# KissCart64-8K-MCU.net
KiCad netlist of a schematic drawn in EAGLE
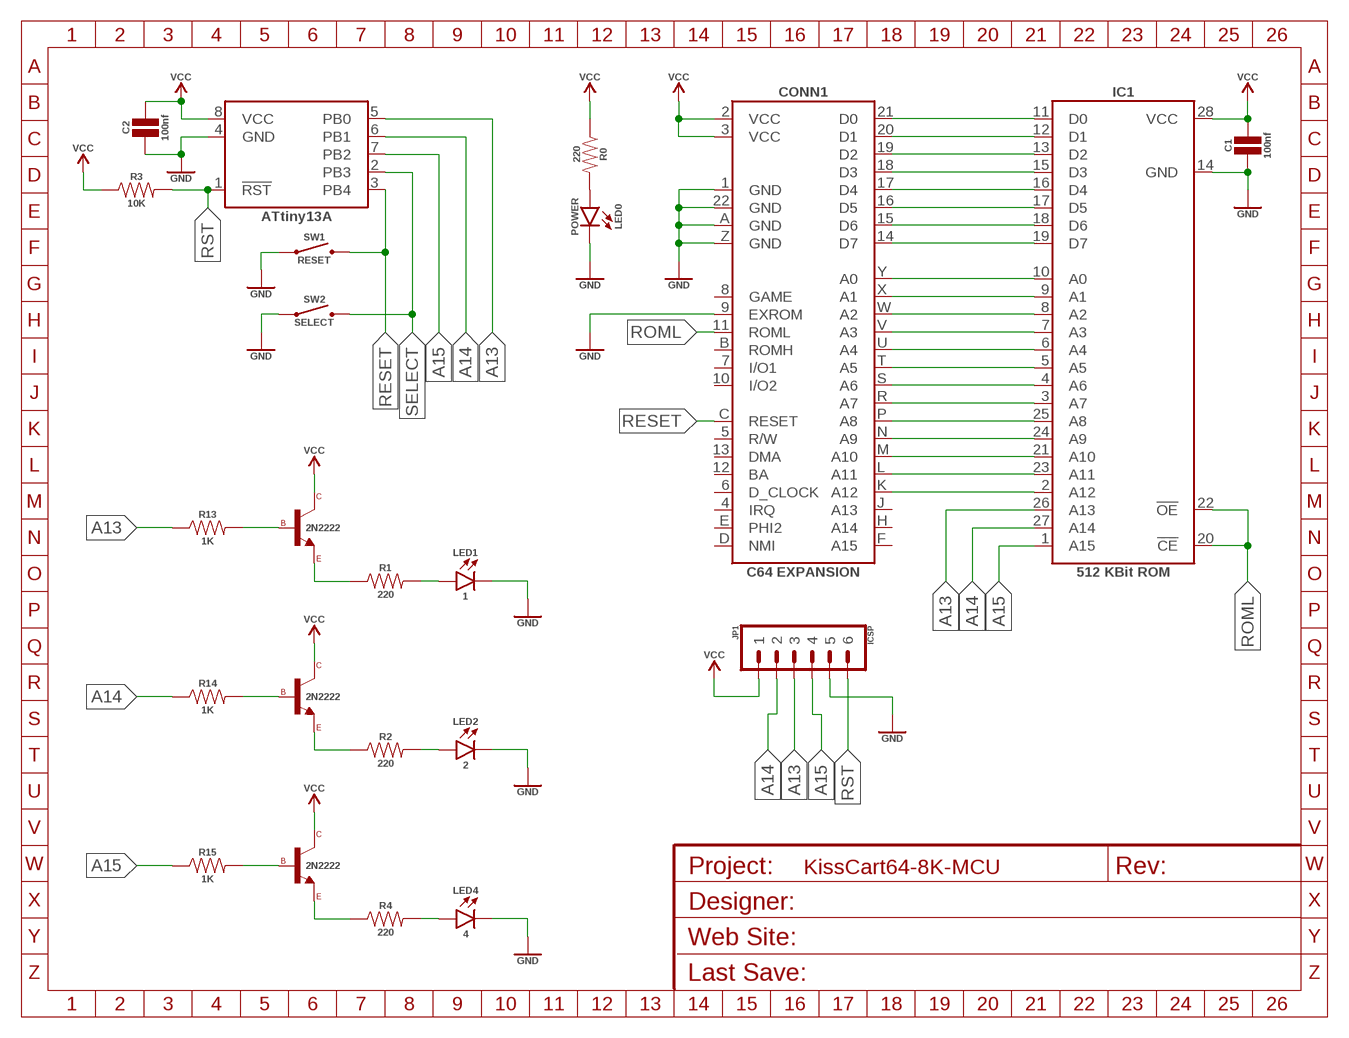
[diagram p0: schematic, sheet 1]

(export (version "E")
  (design (tool "Eeschema 10.0.6"))
  (components
    (comp (ref "C1")
      (value "100nf")
      (footprint "eagle-import:CAPACITOR_CERAMIC_0.2")
      (libsource (lib "eagle-import") (part "CAPACITOR_CERAMIC_0.2"))
    )
    (comp (ref "C2")
      (value "100nf")
      (footprint "eagle-import:CAPACITOR_CERAMIC_1206")
      (libsource (lib "eagle-import") (part "CAPACITOR_CERAMIC_1206"))
    )
    (comp (ref "CONN1")
      (value "C64 EXPANSION")
      (footprint "eagle-import:C64_CARTRIDGE")
      (libsource (lib "eagle-import") (part "C64_CARTDRIGE"))
    )
    (comp (ref "IC1")
      (value "512 KBit ROM")
      (footprint "eagle-import:DIP28W")
      (libsource (lib "eagle-import") (part "27C512_DIP"))
    )
    (comp (ref "IC2")
      (value "ATtiny13A")
      (footprint "eagle-import:SOP08")
      (libsource (lib "eagle-import") (part "ATTINY13A-SU"))
    )
    (comp (ref "JP1")
      (value "ICSP")
      (footprint "eagle-import:HDR_2X03")
      (libsource (lib "eagle-import") (part "HDR_2X03"))
    )
    (comp (ref "LED0")
      (value "POWER")
      (footprint "eagle-import:LED_1206")
      (libsource (lib "eagle-import") (part "LED_NORMAL_1206"))
    )
    (comp (ref "LED1")
      (value "1")
      (footprint "eagle-import:LED_1206")
      (libsource (lib "eagle-import") (part "LED_NORMAL_1206"))
    )
    (comp (ref "LED2")
      (value "2")
      (footprint "eagle-import:LED_1206")
      (libsource (lib "eagle-import") (part "LED_NORMAL_1206"))
    )
    (comp (ref "LED4")
      (value "4")
      (footprint "eagle-import:LED_1206")
      (libsource (lib "eagle-import") (part "LED_NORMAL_1206"))
    )
    (comp (ref "Q1")
      (value "2N2222")
      (footprint "eagle-import:SOT-23")
      (libsource (lib "eagle-import") (part "TRANSISTOR_NPN_MMBT2222A"))
    )
    (comp (ref "Q2")
      (value "2N2222")
      (footprint "eagle-import:SOT-23")
      (libsource (lib "eagle-import") (part "TRANSISTOR_NPN_MMBT2222A"))
    )
    (comp (ref "Q3")
      (value "2N2222")
      (footprint "eagle-import:SOT-23")
      (libsource (lib "eagle-import") (part "TRANSISTOR_NPN_MMBT2222A"))
    )
    (comp (ref "R0")
      (value "220")
      (footprint "eagle-import:RESISTOR_SMT_1206")
      (libsource (lib "eagle-import") (part "RESISTOR_SMT_1206"))
    )
    (comp (ref "R1")
      (value "220")
      (footprint "eagle-import:RESISTOR_SMT_1206")
      (libsource (lib "eagle-import") (part "RESISTOR_SMT_1206"))
    )
    (comp (ref "R2")
      (value "220")
      (footprint "eagle-import:RESISTOR_SMT_1206")
      (libsource (lib "eagle-import") (part "RESISTOR_SMT_1206"))
    )
    (comp (ref "R3")
      (value "10K")
      (footprint "eagle-import:RESISTOR_SMT_1206")
      (libsource (lib "eagle-import") (part "RESISTOR_SMT_1206"))
    )
    (comp (ref "R4")
      (value "220")
      (footprint "eagle-import:RESISTOR_SMT_1206")
      (libsource (lib "eagle-import") (part "RESISTOR_SMT_1206"))
    )
    (comp (ref "R13")
      (value "1K")
      (footprint "eagle-import:RESISTOR_SMT_1206")
      (libsource (lib "eagle-import") (part "RESISTOR_SMT_1206"))
    )
    (comp (ref "R14")
      (value "1K")
      (footprint "eagle-import:RESISTOR_SMT_1206")
      (libsource (lib "eagle-import") (part "RESISTOR_SMT_1206"))
    )
    (comp (ref "R15")
      (value "1K")
      (footprint "eagle-import:RESISTOR_SMT_1206")
      (libsource (lib "eagle-import") (part "RESISTOR_SMT_1206"))
    )
    (comp (ref "SW1")
      (value "RESET")
      (footprint "eagle-import:SWITCH_THT_SIDE")
      (libsource (lib "eagle-import") (part "SWITCH_THT_SIDE"))
    )
    (comp (ref "SW2")
      (value "SELECT")
      (footprint "eagle-import:SWITCH_THT_SIDE")
      (libsource (lib "eagle-import") (part "SWITCH_THT_SIDE"))
    )
  )
  (nets
    (net (code "1") (name "A13") (class "Default")
      (node (ref "IC1") (pin "26") (pinfunction "A13_26") (pintype "input"))
      (node (ref "IC2") (pin "5") (pinfunction "PB0_5") (pintype "bidirectional"))
      (node (ref "JP1") (pin "3") (pinfunction "3_3") (pintype "passive"))
      (node (ref "R13") (pin "1") (pinfunction "1_1") (pintype "passive"))
    )
    (net (code "2") (name "A14") (class "Default")
      (node (ref "IC1") (pin "27") (pinfunction "A14_27") (pintype "input"))
      (node (ref "IC2") (pin "6") (pinfunction "PB1_6") (pintype "bidirectional"))
      (node (ref "JP1") (pin "2") (pinfunction "2_2") (pintype "passive"))
      (node (ref "R14") (pin "1") (pinfunction "1_1") (pintype "passive"))
    )
    (net (code "3") (name "A15") (class "Default")
      (node (ref "IC1") (pin "1") (pinfunction "A15_1") (pintype "input"))
      (node (ref "IC2") (pin "7") (pinfunction "PB2_7") (pintype "bidirectional"))
      (node (ref "JP1") (pin "4") (pinfunction "4_4") (pintype "passive"))
      (node (ref "R15") (pin "1") (pinfunction "1_1") (pintype "passive"))
    )
    (net (code "4") (name "GND") (class "Default")
      (node (ref "C1") (pin "1") (pinfunction "1_1") (pintype "passive"))
      (node (ref "C2") (pin "1") (pinfunction "1_1") (pintype "passive"))
      (node (ref "CONN1") (pin "1") (pinfunction "GND_1") (pintype "bidirectional"))
      (node (ref "CONN1") (pin "22") (pinfunction "GND_22") (pintype "bidirectional"))
      (node (ref "CONN1") (pin "9") (pinfunction "EXROM_9") (pintype "bidirectional"))
      (node (ref "CONN1") (pin "A") (pinfunction "GND_A") (pintype "bidirectional"))
      (node (ref "CONN1") (pin "Z") (pinfunction "GND_Z") (pintype "bidirectional"))
      (node (ref "IC1") (pin "14") (pinfunction "GND_14") (pintype "power_in"))
      (node (ref "IC2") (pin "4") (pinfunction "GND_4") (pintype "power_in"))
      (node (ref "JP1") (pin "5") (pinfunction "5_5") (pintype "passive"))
      (node (ref "LED0") (pin "C") (pinfunction "C_C") (pintype "passive"))
      (node (ref "LED1") (pin "C") (pinfunction "C_C") (pintype "passive"))
      (node (ref "LED2") (pin "C") (pinfunction "C_C") (pintype "passive"))
      (node (ref "LED4") (pin "C") (pinfunction "C_C") (pintype "passive"))
      (node (ref "SW1") (pin "1") (pinfunction "1_1") (pintype "passive"))
      (node (ref "SW2") (pin "1") (pinfunction "1_1") (pintype "passive"))
    )
    (net (code "5") (name "Net-(CONN1-A0)") (class "Default")
      (node (ref "CONN1") (pin "Y") (pinfunction "A0_Y") (pintype "bidirectional"))
      (node (ref "IC1") (pin "10") (pinfunction "A0_10") (pintype "input"))
    )
    (net (code "6") (name "Net-(CONN1-A1)") (class "Default")
      (node (ref "CONN1") (pin "X") (pinfunction "A1_X") (pintype "bidirectional"))
      (node (ref "IC1") (pin "9") (pinfunction "A1_9") (pintype "input"))
    )
    (net (code "7") (name "Net-(CONN1-A2)") (class "Default")
      (node (ref "CONN1") (pin "W") (pinfunction "A2_W") (pintype "bidirectional"))
      (node (ref "IC1") (pin "8") (pinfunction "A2_8") (pintype "input"))
    )
    (net (code "8") (name "Net-(CONN1-A3)") (class "Default")
      (node (ref "CONN1") (pin "V") (pinfunction "A3_V") (pintype "bidirectional"))
      (node (ref "IC1") (pin "7") (pinfunction "A3_7") (pintype "input"))
    )
    (net (code "9") (name "Net-(CONN1-A4)") (class "Default")
      (node (ref "CONN1") (pin "U") (pinfunction "A4_U") (pintype "bidirectional"))
      (node (ref "IC1") (pin "6") (pinfunction "A4_6") (pintype "input"))
    )
    (net (code "10") (name "Net-(CONN1-A5)") (class "Default")
      (node (ref "CONN1") (pin "T") (pinfunction "A5_T") (pintype "bidirectional"))
      (node (ref "IC1") (pin "5") (pinfunction "A5_5") (pintype "input"))
    )
    (net (code "11") (name "Net-(CONN1-A6)") (class "Default")
      (node (ref "CONN1") (pin "S") (pinfunction "A6_S") (pintype "bidirectional"))
      (node (ref "IC1") (pin "4") (pinfunction "A6_4") (pintype "input"))
    )
    (net (code "12") (name "Net-(CONN1-A7)") (class "Default")
      (node (ref "CONN1") (pin "R") (pinfunction "A7_R") (pintype "bidirectional"))
      (node (ref "IC1") (pin "3") (pinfunction "A7_3") (pintype "input"))
    )
    (net (code "13") (name "Net-(CONN1-A8)") (class "Default")
      (node (ref "CONN1") (pin "P") (pinfunction "A8_P") (pintype "bidirectional"))
      (node (ref "IC1") (pin "25") (pinfunction "A8_25") (pintype "input"))
    )
    (net (code "14") (name "Net-(CONN1-A9)") (class "Default")
      (node (ref "CONN1") (pin "N") (pinfunction "A9_N") (pintype "bidirectional"))
      (node (ref "IC1") (pin "24") (pinfunction "A9_24") (pintype "input"))
    )
    (net (code "15") (name "Net-(CONN1-A10)") (class "Default")
      (node (ref "CONN1") (pin "M") (pinfunction "A10_M") (pintype "bidirectional"))
      (node (ref "IC1") (pin "21") (pinfunction "A10_21") (pintype "input"))
    )
    (net (code "16") (name "Net-(CONN1-A11)") (class "Default")
      (node (ref "CONN1") (pin "L") (pinfunction "A11_L") (pintype "bidirectional"))
      (node (ref "IC1") (pin "23") (pinfunction "A11_23") (pintype "input"))
    )
    (net (code "17") (name "Net-(CONN1-A12)") (class "Default")
      (node (ref "CONN1") (pin "K") (pinfunction "A12_K") (pintype "bidirectional"))
      (node (ref "IC1") (pin "2") (pinfunction "A12_2") (pintype "input"))
    )
    (net (code "18") (name "Net-(CONN1-D0)") (class "Default")
      (node (ref "CONN1") (pin "21") (pinfunction "D0_21") (pintype "bidirectional"))
      (node (ref "IC1") (pin "11") (pinfunction "D0_11") (pintype "tri_state"))
    )
    (net (code "19") (name "Net-(CONN1-D1)") (class "Default")
      (node (ref "CONN1") (pin "20") (pinfunction "D1_20") (pintype "bidirectional"))
      (node (ref "IC1") (pin "12") (pinfunction "D1_12") (pintype "tri_state"))
    )
    (net (code "20") (name "Net-(CONN1-D2)") (class "Default")
      (node (ref "CONN1") (pin "19") (pinfunction "D2_19") (pintype "bidirectional"))
      (node (ref "IC1") (pin "13") (pinfunction "D2_13") (pintype "tri_state"))
    )
    (net (code "21") (name "Net-(CONN1-D3)") (class "Default")
      (node (ref "CONN1") (pin "18") (pinfunction "D3_18") (pintype "bidirectional"))
      (node (ref "IC1") (pin "15") (pinfunction "D3_15") (pintype "tri_state"))
    )
    (net (code "22") (name "Net-(CONN1-D4)") (class "Default")
      (node (ref "CONN1") (pin "17") (pinfunction "D4_17") (pintype "bidirectional"))
      (node (ref "IC1") (pin "16") (pinfunction "D4_16") (pintype "tri_state"))
    )
    (net (code "23") (name "Net-(CONN1-D5)") (class "Default")
      (node (ref "CONN1") (pin "16") (pinfunction "D5_16") (pintype "bidirectional"))
      (node (ref "IC1") (pin "17") (pinfunction "D5_17") (pintype "tri_state"))
    )
    (net (code "24") (name "Net-(CONN1-D6)") (class "Default")
      (node (ref "CONN1") (pin "15") (pinfunction "D6_15") (pintype "bidirectional"))
      (node (ref "IC1") (pin "18") (pinfunction "D6_18") (pintype "tri_state"))
    )
    (net (code "25") (name "Net-(CONN1-D7)") (class "Default")
      (node (ref "CONN1") (pin "14") (pinfunction "D7_14") (pintype "bidirectional"))
      (node (ref "IC1") (pin "19") (pinfunction "D7_19") (pintype "tri_state"))
    )
    (net (code "26") (name "Net-(LED0-PadA)") (class "Default")
      (node (ref "LED0") (pin "A") (pinfunction "A_A") (pintype "passive"))
      (node (ref "R0") (pin "2") (pinfunction "2_2") (pintype "passive"))
    )
    (net (code "27") (name "Net-(LED1-PadA)") (class "Default")
      (node (ref "LED1") (pin "A") (pinfunction "A_A") (pintype "passive"))
      (node (ref "R1") (pin "2") (pinfunction "2_2") (pintype "passive"))
    )
    (net (code "28") (name "Net-(LED2-PadA)") (class "Default")
      (node (ref "LED2") (pin "A") (pinfunction "A_A") (pintype "passive"))
      (node (ref "R2") (pin "2") (pinfunction "2_2") (pintype "passive"))
    )
    (net (code "29") (name "Net-(LED4-PadA)") (class "Default")
      (node (ref "LED4") (pin "A") (pinfunction "A_A") (pintype "passive"))
      (node (ref "R4") (pin "2") (pinfunction "2_2") (pintype "passive"))
    )
    (net (code "30") (name "Net-(Q1-BASE)") (class "Default")
      (node (ref "Q1") (pin "1") (pinfunction "BASE_1") (pintype "passive"))
      (node (ref "R13") (pin "2") (pinfunction "2_2") (pintype "passive"))
    )
    (net (code "31") (name "Net-(Q1-EMITTER)") (class "Default")
      (node (ref "Q1") (pin "2") (pinfunction "EMITTER_2") (pintype "passive"))
      (node (ref "R1") (pin "1") (pinfunction "1_1") (pintype "passive"))
    )
    (net (code "32") (name "Net-(Q2-BASE)") (class "Default")
      (node (ref "Q2") (pin "1") (pinfunction "BASE_1") (pintype "passive"))
      (node (ref "R14") (pin "2") (pinfunction "2_2") (pintype "passive"))
    )
    (net (code "33") (name "Net-(Q2-EMITTER)") (class "Default")
      (node (ref "Q2") (pin "2") (pinfunction "EMITTER_2") (pintype "passive"))
      (node (ref "R2") (pin "1") (pinfunction "1_1") (pintype "passive"))
    )
    (net (code "34") (name "Net-(Q3-BASE)") (class "Default")
      (node (ref "Q3") (pin "1") (pinfunction "BASE_1") (pintype "passive"))
      (node (ref "R15") (pin "2") (pinfunction "2_2") (pintype "passive"))
    )
    (net (code "35") (name "Net-(Q3-EMITTER)") (class "Default")
      (node (ref "Q3") (pin "2") (pinfunction "EMITTER_2") (pintype "passive"))
      (node (ref "R4") (pin "1") (pinfunction "1_1") (pintype "passive"))
    )
    (net (code "36") (name "RESET") (class "Default")
      (node (ref "CONN1") (pin "C") (pinfunction "RESET_C") (pintype "bidirectional"))
      (node (ref "IC2") (pin "3") (pinfunction "PB4_3") (pintype "bidirectional"))
      (node (ref "SW1") (pin "2") (pinfunction "2_2") (pintype "passive"))
    )
    (net (code "37") (name "ROML") (class "Default")
      (node (ref "CONN1") (pin "11") (pinfunction "ROML_11") (pintype "bidirectional"))
      (node (ref "IC1") (pin "20") (pinfunction "~{CE}_20") (pintype "input"))
      (node (ref "IC1") (pin "22") (pinfunction "~{OE}_22") (pintype "input"))
    )
    (net (code "38") (name "RST") (class "Default")
      (node (ref "IC2") (pin "1") (pinfunction "~{RST}_1") (pintype "bidirectional"))
      (node (ref "JP1") (pin "6") (pinfunction "6_6") (pintype "passive"))
      (node (ref "R3") (pin "2") (pinfunction "2_2") (pintype "passive"))
    )
    (net (code "39") (name "SELECT") (class "Default")
      (node (ref "IC2") (pin "2") (pinfunction "PB3_2") (pintype "bidirectional"))
      (node (ref "SW2") (pin "2") (pinfunction "2_2") (pintype "passive"))
    )
    (net (code "40") (name "VCC") (class "Default")
      (node (ref "C1") (pin "2") (pinfunction "2_2") (pintype "passive"))
      (node (ref "C2") (pin "2") (pinfunction "2_2") (pintype "passive"))
      (node (ref "CONN1") (pin "2") (pinfunction "VCC_2") (pintype "bidirectional"))
      (node (ref "CONN1") (pin "3") (pinfunction "VCC_3") (pintype "bidirectional"))
      (node (ref "IC1") (pin "28") (pinfunction "VCC_28") (pintype "power_in"))
      (node (ref "IC2") (pin "8") (pinfunction "VCC_8") (pintype "power_in"))
      (node (ref "JP1") (pin "1") (pinfunction "1_1") (pintype "passive"))
      (node (ref "Q1") (pin "3") (pinfunction "COLLECTOR_3") (pintype "passive"))
      (node (ref "Q2") (pin "3") (pinfunction "COLLECTOR_3") (pintype "passive"))
      (node (ref "Q3") (pin "3") (pinfunction "COLLECTOR_3") (pintype "passive"))
      (node (ref "R0") (pin "1") (pinfunction "1_1") (pintype "passive"))
      (node (ref "R3") (pin "1") (pinfunction "1_1") (pintype "passive"))
    )
    (net (code "41") (name "unconnected-(CONN1-A13-PadJ)") (class "Default")
      (node (ref "CONN1") (pin "J") (pinfunction "A13_J") (pintype "bidirectional"))
    )
    (net (code "42") (name "unconnected-(CONN1-A14-PadH)") (class "Default")
      (node (ref "CONN1") (pin "H") (pinfunction "A14_H") (pintype "bidirectional"))
    )
    (net (code "43") (name "unconnected-(CONN1-A15-PadF)") (class "Default")
      (node (ref "CONN1") (pin "F") (pinfunction "A15_F") (pintype "bidirectional"))
    )
    (net (code "44") (name "unconnected-(CONN1-BA-Pad12)") (class "Default")
      (node (ref "CONN1") (pin "12") (pinfunction "BA_12") (pintype "bidirectional"))
    )
    (net (code "45") (name "unconnected-(CONN1-DMA-Pad13)") (class "Default")
      (node (ref "CONN1") (pin "13") (pinfunction "DMA_13") (pintype "bidirectional"))
    )
    (net (code "46") (name "unconnected-(CONN1-D_CLOCK-Pad6)") (class "Default")
      (node (ref "CONN1") (pin "6") (pinfunction "D_CLOCK_6") (pintype "bidirectional"))
    )
    (net (code "47") (name "unconnected-(CONN1-GAME-Pad8)") (class "Default")
      (node (ref "CONN1") (pin "8") (pinfunction "GAME_8") (pintype "bidirectional"))
    )
    (net (code "48") (name "unconnected-(CONN1-IRQ-Pad4)") (class "Default")
      (node (ref "CONN1") (pin "4") (pinfunction "IRQ_4") (pintype "bidirectional"))
    )
    (net (code "49") (name "unconnected-(CONN1-I{slash}O1-Pad7)") (class "Default")
      (node (ref "CONN1") (pin "7") (pinfunction "I/O1_7") (pintype "bidirectional"))
    )
    (net (code "50") (name "unconnected-(CONN1-I{slash}O2-Pad10)") (class "Default")
      (node (ref "CONN1") (pin "10") (pinfunction "I/O2_10") (pintype "bidirectional"))
    )
    (net (code "51") (name "unconnected-(CONN1-NMI-PadD)") (class "Default")
      (node (ref "CONN1") (pin "D") (pinfunction "NMI_D") (pintype "bidirectional"))
    )
    (net (code "52") (name "unconnected-(CONN1-PHI2-PadE)") (class "Default")
      (node (ref "CONN1") (pin "E") (pinfunction "PHI2_E") (pintype "bidirectional"))
    )
    (net (code "53") (name "unconnected-(CONN1-ROMH-PadB)") (class "Default")
      (node (ref "CONN1") (pin "B") (pinfunction "ROMH_B") (pintype "bidirectional"))
    )
    (net (code "54") (name "unconnected-(CONN1-R{slash}W-Pad5)") (class "Default")
      (node (ref "CONN1") (pin "5") (pinfunction "R/W_5") (pintype "bidirectional"))
    )
  )
)
